# brain.net
KiCad netlist of a schematic drawn in EAGLE
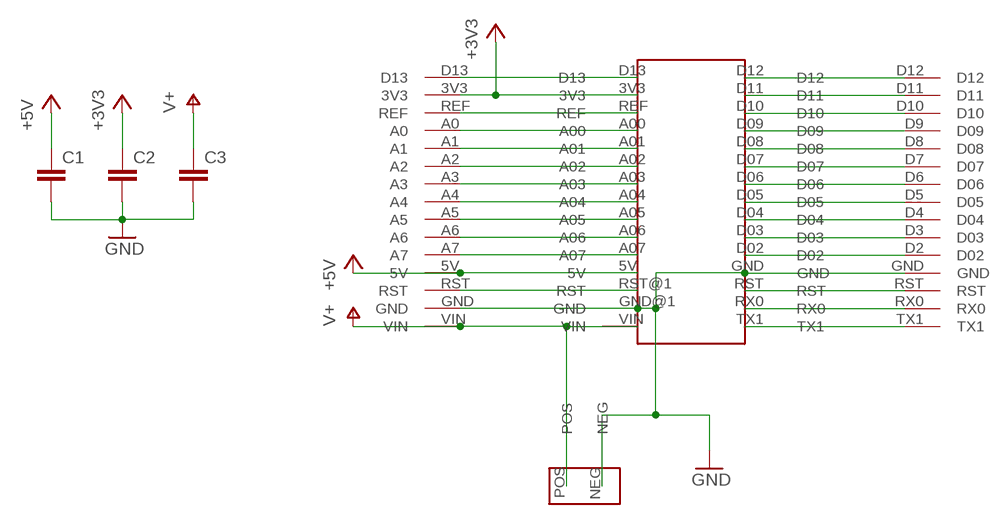
[diagram p0: schematic, sheet 1]

(export (version "E")
  (design (tool "Eeschema 10.0.6"))
  (components
    (comp (ref "C1")
      (value "C-EU050-025X075")
      (footprint "eagle-import:C050-025X075")
      (libsource (lib "eagle-import") (part "C-EU050-025X075"))
    )
    (comp (ref "C2")
      (value "C-EU050-025X075")
      (footprint "eagle-import:C050-025X075")
      (libsource (lib "eagle-import") (part "C-EU050-025X075"))
    )
    (comp (ref "C3")
      (value "C-EU050-025X075")
      (footprint "eagle-import:C050-025X075")
      (libsource (lib "eagle-import") (part "C-EU050-025X075"))
    )
    (comp (ref "U$1")
      (value "ARDUINO-NANO-V3")
      (footprint "eagle-import:ARDUINO-NANO-V3")
      (libsource (lib "eagle-import") (part "ARDUINO-NANO-V3"))
    )
    (comp (ref "U$2")
      (value "ARDUINO-NANO-JUMPER-1")
      (footprint "eagle-import:ARDUINO-NANO-JUMPER-1")
      (libsource (lib "eagle-import") (part "ARDUINO-NANO-JUMPER-1"))
    )
    (comp (ref "U$3")
      (value "POWER-IN")
      (footprint "eagle-import:POWER-IN")
      (libsource (lib "eagle-import") (part "POWER-IN"))
    )
    (comp (ref "U$5")
      (value "ARDUINO-NANO-JUMPER-2")
      (footprint "eagle-import:ARDUINO-NANO-JUMPER-2")
      (libsource (lib "eagle-import") (part "ARDUINO-NANO-JUMPER-2"))
    )
  )
  (nets
    (net (code "1") (name "+3V3") (class "Default")
      (node (ref "C2") (pin "1") (pinfunction "1_1") (pintype "passive"))
      (node (ref "U$1") (pin "3V3") (pinfunction "3V3_3V3") (pintype "bidirectional"))
      (node (ref "U$5") (pin "3V3") (pinfunction "3V3_3V3") (pintype "bidirectional"))
    )
    (net (code "2") (name "+5V") (class "Default")
      (node (ref "C1") (pin "1") (pinfunction "1_1") (pintype "passive"))
      (node (ref "U$1") (pin "5V") (pinfunction "5V_5V") (pintype "bidirectional"))
      (node (ref "U$5") (pin "5V") (pinfunction "5V_5V") (pintype "bidirectional"))
    )
    (net (code "3") (name "/RST") (class "Default")
      (node (ref "U$1") (pin "RST") (pinfunction "RST_RST") (pintype "bidirectional"))
      (node (ref "U$1") (pin "RST@1") (pinfunction "RST_RST@1") (pintype "bidirectional"))
      (node (ref "U$2") (pin "RST") (pinfunction "RST_RST") (pintype "bidirectional"))
      (node (ref "U$5") (pin "RST") (pinfunction "RST_RST") (pintype "bidirectional"))
    )
    (net (code "4") (name "GND") (class "Default")
      (node (ref "C1") (pin "2") (pinfunction "2_2") (pintype "passive"))
      (node (ref "C2") (pin "2") (pinfunction "2_2") (pintype "passive"))
      (node (ref "C3") (pin "2") (pinfunction "2_2") (pintype "passive"))
      (node (ref "U$1") (pin "GND") (pinfunction "GND_GND") (pintype "bidirectional"))
      (node (ref "U$1") (pin "GND@1") (pinfunction "GND_GND@1") (pintype "bidirectional"))
      (node (ref "U$2") (pin "GND") (pinfunction "GND_GND") (pintype "bidirectional"))
      (node (ref "U$3") (pin "NEG") (pinfunction "NEG_NEG") (pintype "bidirectional"))
      (node (ref "U$5") (pin "GND") (pinfunction "GND_GND") (pintype "bidirectional"))
    )
    (net (code "5") (name "Net-(U$1-PadA00)") (class "Default")
      (node (ref "U$1") (pin "A00") (pinfunction "A00_A00") (pintype "bidirectional"))
      (node (ref "U$5") (pin "A0") (pinfunction "A0_A0") (pintype "bidirectional"))
    )
    (net (code "6") (name "Net-(U$1-PadA01)") (class "Default")
      (node (ref "U$1") (pin "A01") (pinfunction "A01_A01") (pintype "bidirectional"))
      (node (ref "U$5") (pin "A1") (pinfunction "A1_A1") (pintype "bidirectional"))
    )
    (net (code "7") (name "Net-(U$1-PadA02)") (class "Default")
      (node (ref "U$1") (pin "A02") (pinfunction "A02_A02") (pintype "bidirectional"))
      (node (ref "U$5") (pin "A2") (pinfunction "A2_A2") (pintype "bidirectional"))
    )
    (net (code "8") (name "Net-(U$1-PadA03)") (class "Default")
      (node (ref "U$1") (pin "A03") (pinfunction "A03_A03") (pintype "bidirectional"))
      (node (ref "U$5") (pin "A3") (pinfunction "A3_A3") (pintype "bidirectional"))
    )
    (net (code "9") (name "Net-(U$1-PadA04)") (class "Default")
      (node (ref "U$1") (pin "A04") (pinfunction "A04_A04") (pintype "bidirectional"))
      (node (ref "U$5") (pin "A4") (pinfunction "A4_A4") (pintype "bidirectional"))
    )
    (net (code "10") (name "Net-(U$1-PadA05)") (class "Default")
      (node (ref "U$1") (pin "A05") (pinfunction "A05_A05") (pintype "bidirectional"))
      (node (ref "U$5") (pin "A5") (pinfunction "A5_A5") (pintype "bidirectional"))
    )
    (net (code "11") (name "Net-(U$1-PadA06)") (class "Default")
      (node (ref "U$1") (pin "A06") (pinfunction "A06_A06") (pintype "bidirectional"))
      (node (ref "U$5") (pin "A6") (pinfunction "A6_A6") (pintype "bidirectional"))
    )
    (net (code "12") (name "Net-(U$1-PadA07)") (class "Default")
      (node (ref "U$1") (pin "A07") (pinfunction "A07_A07") (pintype "bidirectional"))
      (node (ref "U$5") (pin "A7") (pinfunction "A7_A7") (pintype "bidirectional"))
    )
    (net (code "13") (name "Net-(U$1-PadD10)") (class "Default")
      (node (ref "U$1") (pin "D10") (pinfunction "D10_D10") (pintype "bidirectional"))
      (node (ref "U$2") (pin "D10") (pinfunction "D10_D10") (pintype "bidirectional"))
    )
    (net (code "14") (name "Net-(U$1-PadD11)") (class "Default")
      (node (ref "U$1") (pin "D11") (pinfunction "D11_D11") (pintype "bidirectional"))
      (node (ref "U$2") (pin "D11") (pinfunction "D11_D11") (pintype "bidirectional"))
    )
    (net (code "15") (name "Net-(U$1-PadD12)") (class "Default")
      (node (ref "U$1") (pin "D12") (pinfunction "D12_D12") (pintype "bidirectional"))
      (node (ref "U$2") (pin "D12") (pinfunction "D12_D12") (pintype "bidirectional"))
    )
    (net (code "16") (name "Net-(U$1-PadD13)") (class "Default")
      (node (ref "U$1") (pin "D13") (pinfunction "D13_D13") (pintype "bidirectional"))
      (node (ref "U$5") (pin "D13") (pinfunction "D13_D13") (pintype "bidirectional"))
    )
    (net (code "17") (name "Net-(U$1-PadREF)") (class "Default")
      (node (ref "U$1") (pin "REF") (pinfunction "REF_REF") (pintype "bidirectional"))
      (node (ref "U$5") (pin "REF") (pinfunction "REF_REF") (pintype "bidirectional"))
    )
    (net (code "18") (name "Net-(U$1-PadRX0)") (class "Default")
      (node (ref "U$1") (pin "RX0") (pinfunction "RX0_RX0") (pintype "bidirectional"))
      (node (ref "U$2") (pin "RX0") (pinfunction "RX0_RX0") (pintype "bidirectional"))
    )
    (net (code "19") (name "Net-(U$1-PadTX1)") (class "Default")
      (node (ref "U$1") (pin "TX1") (pinfunction "TX1_TX1") (pintype "bidirectional"))
      (node (ref "U$2") (pin "TX1") (pinfunction "TX1_TX1") (pintype "bidirectional"))
    )
    (net (code "20") (name "Net-(U$2-D02)") (class "Default")
      (node (ref "U$1") (pin "D02") (pinfunction "D02_D02") (pintype "bidirectional"))
      (node (ref "U$2") (pin "D2") (pinfunction "D02_D2") (pintype "bidirectional"))
    )
    (net (code "21") (name "Net-(U$2-D03)") (class "Default")
      (node (ref "U$1") (pin "D03") (pinfunction "D03_D03") (pintype "bidirectional"))
      (node (ref "U$2") (pin "D3") (pinfunction "D03_D3") (pintype "bidirectional"))
    )
    (net (code "22") (name "Net-(U$2-D04)") (class "Default")
      (node (ref "U$1") (pin "D04") (pinfunction "D04_D04") (pintype "bidirectional"))
      (node (ref "U$2") (pin "D4") (pinfunction "D04_D4") (pintype "bidirectional"))
    )
    (net (code "23") (name "Net-(U$2-D05)") (class "Default")
      (node (ref "U$1") (pin "D05") (pinfunction "D05_D05") (pintype "bidirectional"))
      (node (ref "U$2") (pin "D5") (pinfunction "D05_D5") (pintype "bidirectional"))
    )
    (net (code "24") (name "Net-(U$2-D06)") (class "Default")
      (node (ref "U$1") (pin "D06") (pinfunction "D06_D06") (pintype "bidirectional"))
      (node (ref "U$2") (pin "D6") (pinfunction "D06_D6") (pintype "bidirectional"))
    )
    (net (code "25") (name "Net-(U$2-D07)") (class "Default")
      (node (ref "U$1") (pin "D07") (pinfunction "D07_D07") (pintype "bidirectional"))
      (node (ref "U$2") (pin "D7") (pinfunction "D07_D7") (pintype "bidirectional"))
    )
    (net (code "26") (name "Net-(U$2-D08)") (class "Default")
      (node (ref "U$1") (pin "D08") (pinfunction "D08_D08") (pintype "bidirectional"))
      (node (ref "U$2") (pin "D8") (pinfunction "D08_D8") (pintype "bidirectional"))
    )
    (net (code "27") (name "Net-(U$2-D09)") (class "Default")
      (node (ref "U$1") (pin "D09") (pinfunction "D09_D09") (pintype "bidirectional"))
      (node (ref "U$2") (pin "D9") (pinfunction "D09_D9") (pintype "bidirectional"))
    )
    (net (code "28") (name "V+") (class "Default")
      (node (ref "C3") (pin "1") (pinfunction "1_1") (pintype "passive"))
      (node (ref "U$1") (pin "VIN") (pinfunction "VIN_VIN") (pintype "bidirectional"))
      (node (ref "U$3") (pin "POS") (pinfunction "POS_POS") (pintype "bidirectional"))
      (node (ref "U$5") (pin "VIN") (pinfunction "VIN_VIN") (pintype "bidirectional"))
    )
  )
)
